# SCH_OnBoard_2024-10-12.net
KiCad netlist of a schematic drawn in EasyEDA
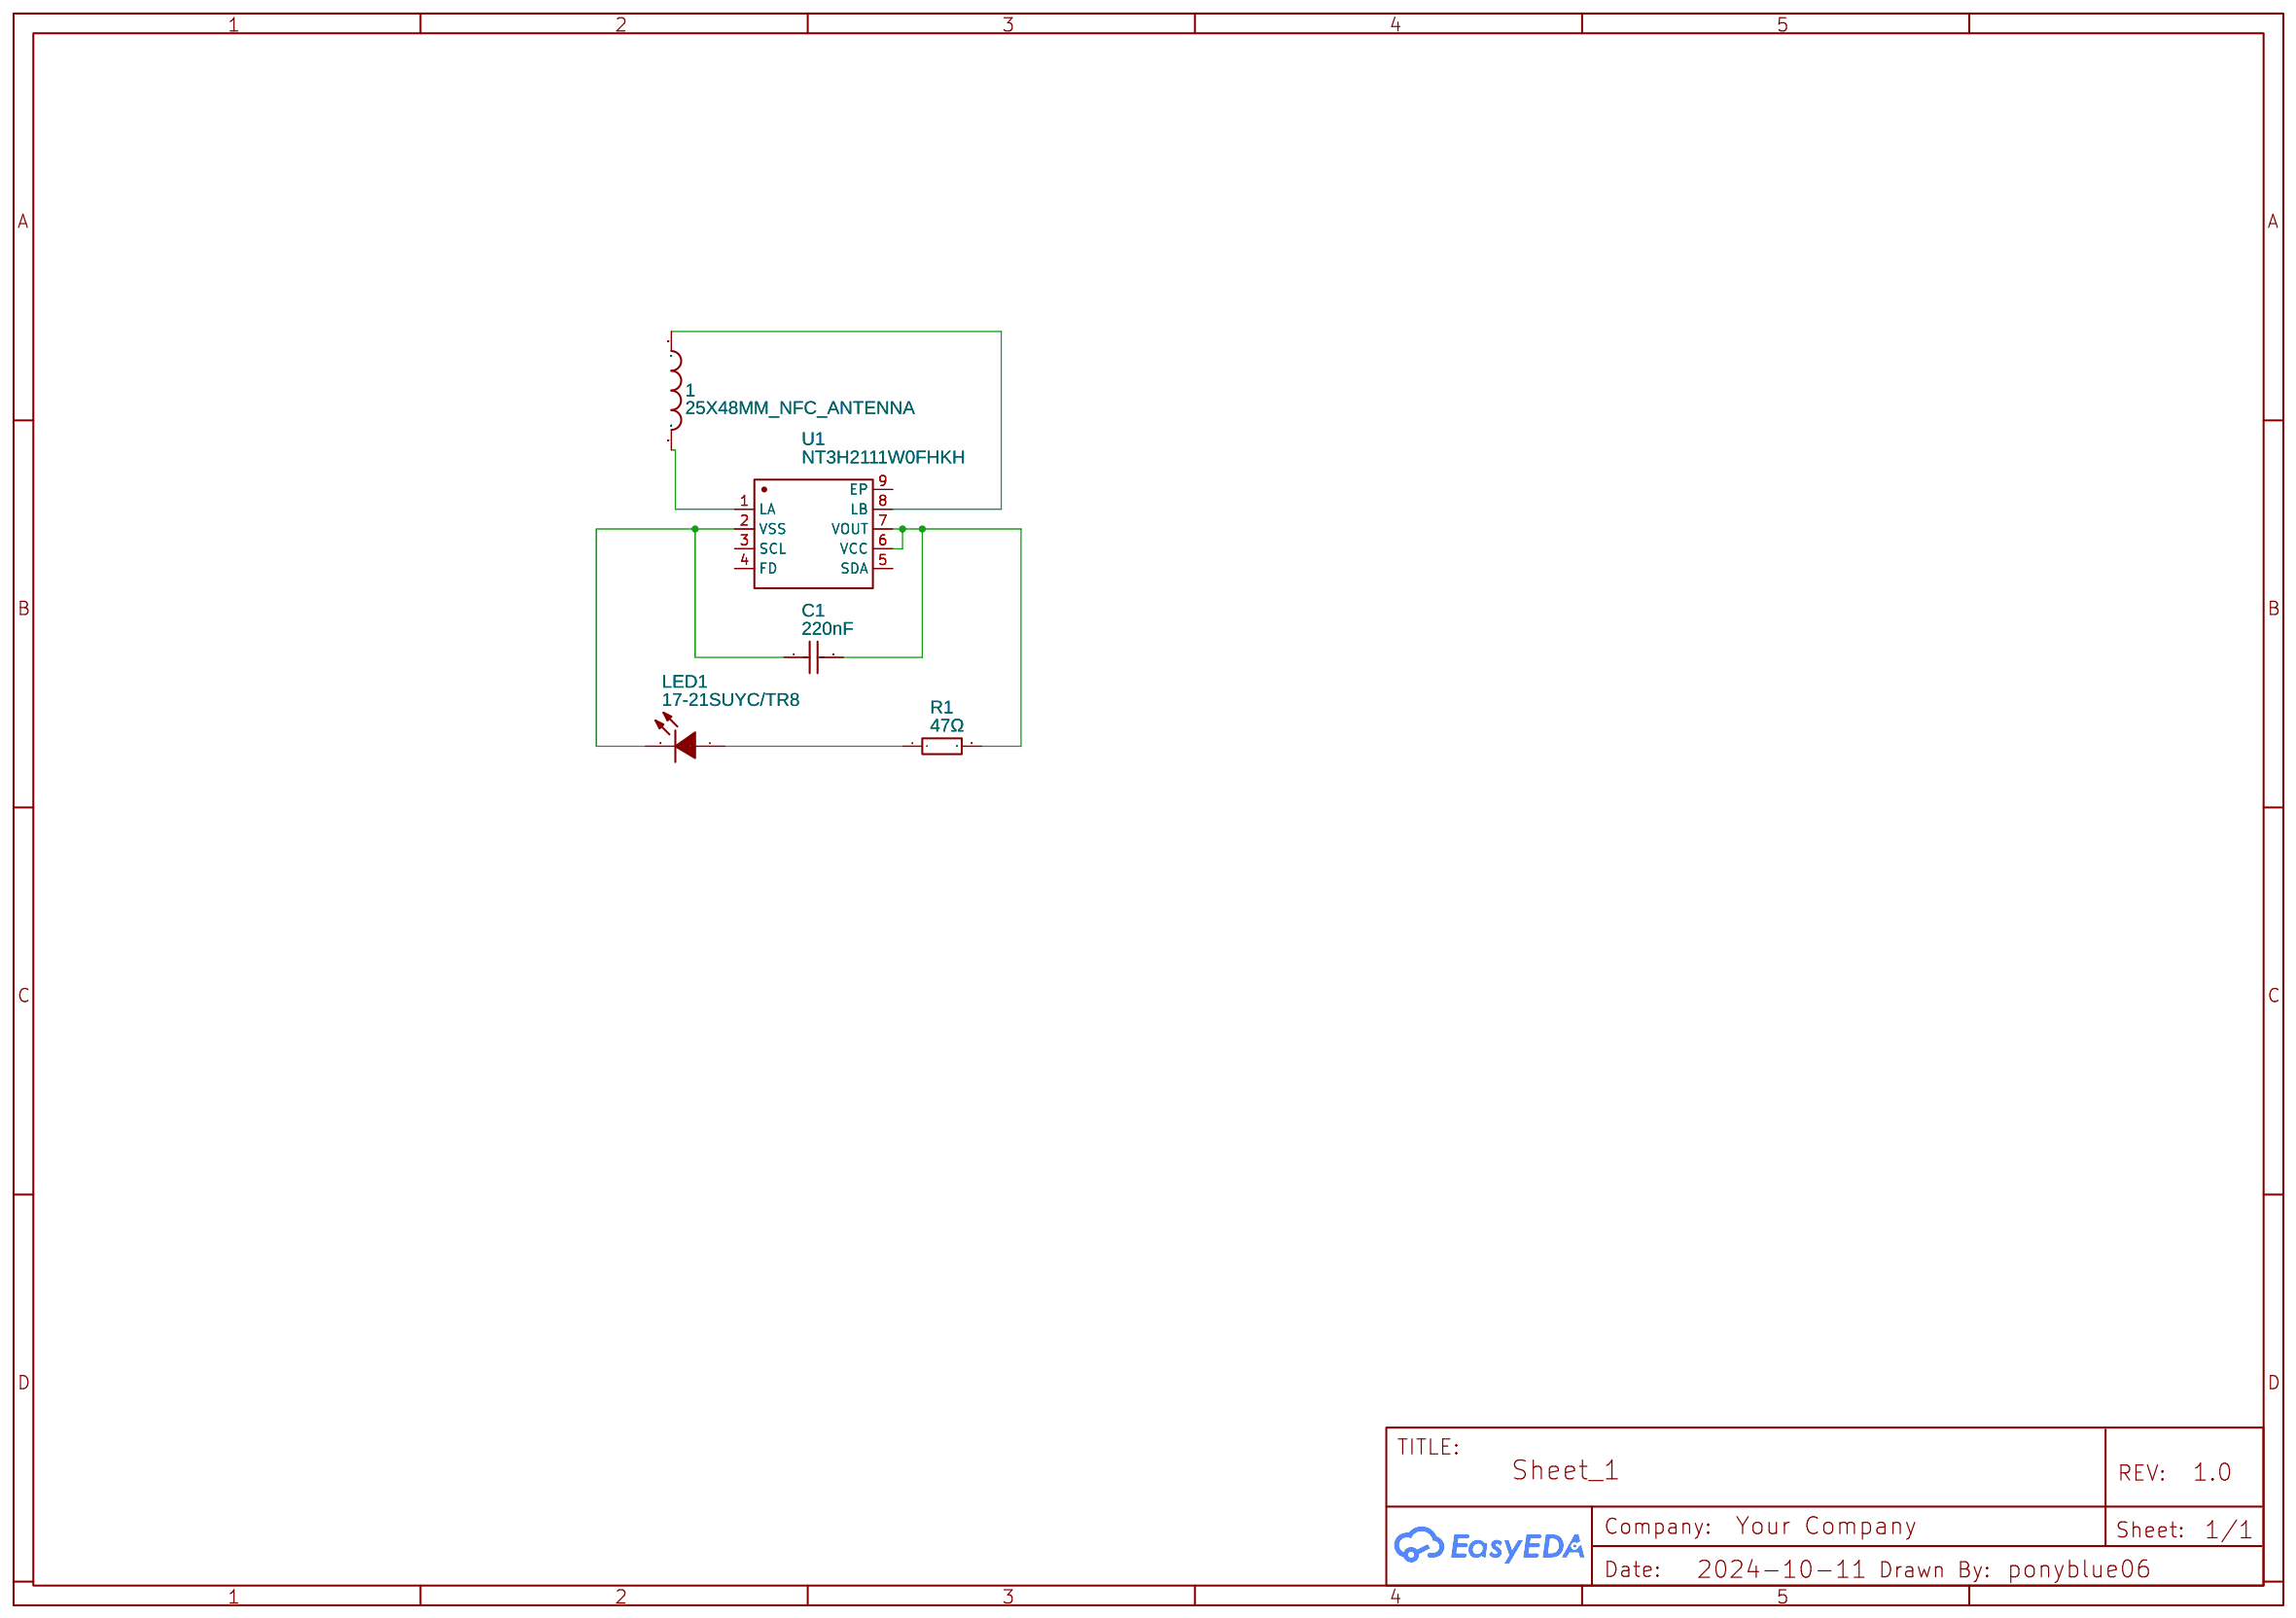
[diagram p0: schematic sheet]

(export (version "E")
  (design (tool "Eeschema 10.0.6"))
  (components
    (comp (ref "1") (value "25X48MM_NFC_ANTENNA") (libsource (lib "") (part "25X48MM_NFC_ANTENNA")))
    (comp (ref "C1")
      (value "220nF")
      (fields
        (field (name "Manufacturer Part") "CL10B224KA8NNNC")
        (field (name "Manufacturer") "SAMSUNG(三星)")
      )
      (libsource (lib "") (part "CL10B224KA8NNNC"))
    )
    (comp (ref "LED1")
      (value "17-21SUYC/TR8")
      (fields (field (name "Manufacturer Part") "KT-0805黄灯") (field (name "Manufacturer") "KENTO"))
      (libsource (lib "") (part "17-21SUYC/TR8"))
    )
    (comp (ref "R1")
      (value "47Ω")
      (fields
        (field (name "Manufacturer Part") "0603WAF470JT5E")
        (field (name "Manufacturer") "UNI-ROYAL(厚声)")
      )
      (libsource (lib "") (part "0603WAF470JT5E"))
    )
    (comp (ref "U1")
      (value "NT3H2111W0FHKH")
      (fields (field (name "Manufacturer") "NXP(恩智浦)"))
      (libsource (lib "") (part "NT3H2111W0FHKH"))
    )
  )
  (nets
    (net (code "1") (name "Net-(LED1-+)") (class "Default")
      (node (ref "LED1") (pin "1") (pinfunction "+_1") (pintype "unspecified"))
      (node (ref "R1") (pin "1") (pinfunction "1_1") (pintype "input"))
    )
    (net (code "2") (name "Net-(LED1--)") (class "Default")
      (node (ref "C1") (pin "1") (pinfunction "1_1") (pintype "input"))
      (node (ref "LED1") (pin "2") (pinfunction "-_2") (pintype "unspecified"))
      (node (ref "U1") (pin "2") (pinfunction "VSS_2") (pintype "unspecified"))
    )
    (net (code "3") (name "Net-(U1-LA)") (class "Default")
      (node (ref "1") (pin "P$2") (pinfunction "P$2_P$2") (pintype "bidirectional"))
      (node (ref "U1") (pin "1") (pinfunction "LA_1") (pintype "unspecified"))
    )
    (net (code "4") (name "Net-(U1-LB)") (class "Default")
      (node (ref "1") (pin "P$1") (pinfunction "P$1_P$1") (pintype "bidirectional"))
      (node (ref "U1") (pin "8") (pinfunction "LB_8") (pintype "unspecified"))
    )
    (net (code "5") (name "Net-(U1-VCC)") (class "Default")
      (node (ref "C1") (pin "2") (pinfunction "2_2") (pintype "input"))
      (node (ref "R1") (pin "2") (pinfunction "2_2") (pintype "input"))
      (node (ref "U1") (pin "6") (pinfunction "VCC_6") (pintype "unspecified"))
      (node (ref "U1") (pin "7") (pinfunction "VOUT_7") (pintype "unspecified"))
    )
    (net (code "6") (name "unconnected-(U1-EP-Pad9)") (class "Default")
      (node (ref "U1") (pin "9") (pinfunction "EP_9") (pintype "unspecified"))
    )
    (net (code "7") (name "unconnected-(U1-FD-Pad4)") (class "Default")
      (node (ref "U1") (pin "4") (pinfunction "FD_4") (pintype "unspecified"))
    )
    (net (code "8") (name "unconnected-(U1-SCL-Pad3)") (class "Default")
      (node (ref "U1") (pin "3") (pinfunction "SCL_3") (pintype "unspecified"))
    )
    (net (code "9") (name "unconnected-(U1-SDA-Pad5)") (class "Default")
      (node (ref "U1") (pin "5") (pinfunction "SDA_5") (pintype "unspecified"))
    )
  )
)
